# Arduino_S3v3_R2_ft3.net
KiCad netlist of a schematic drawn in EAGLE
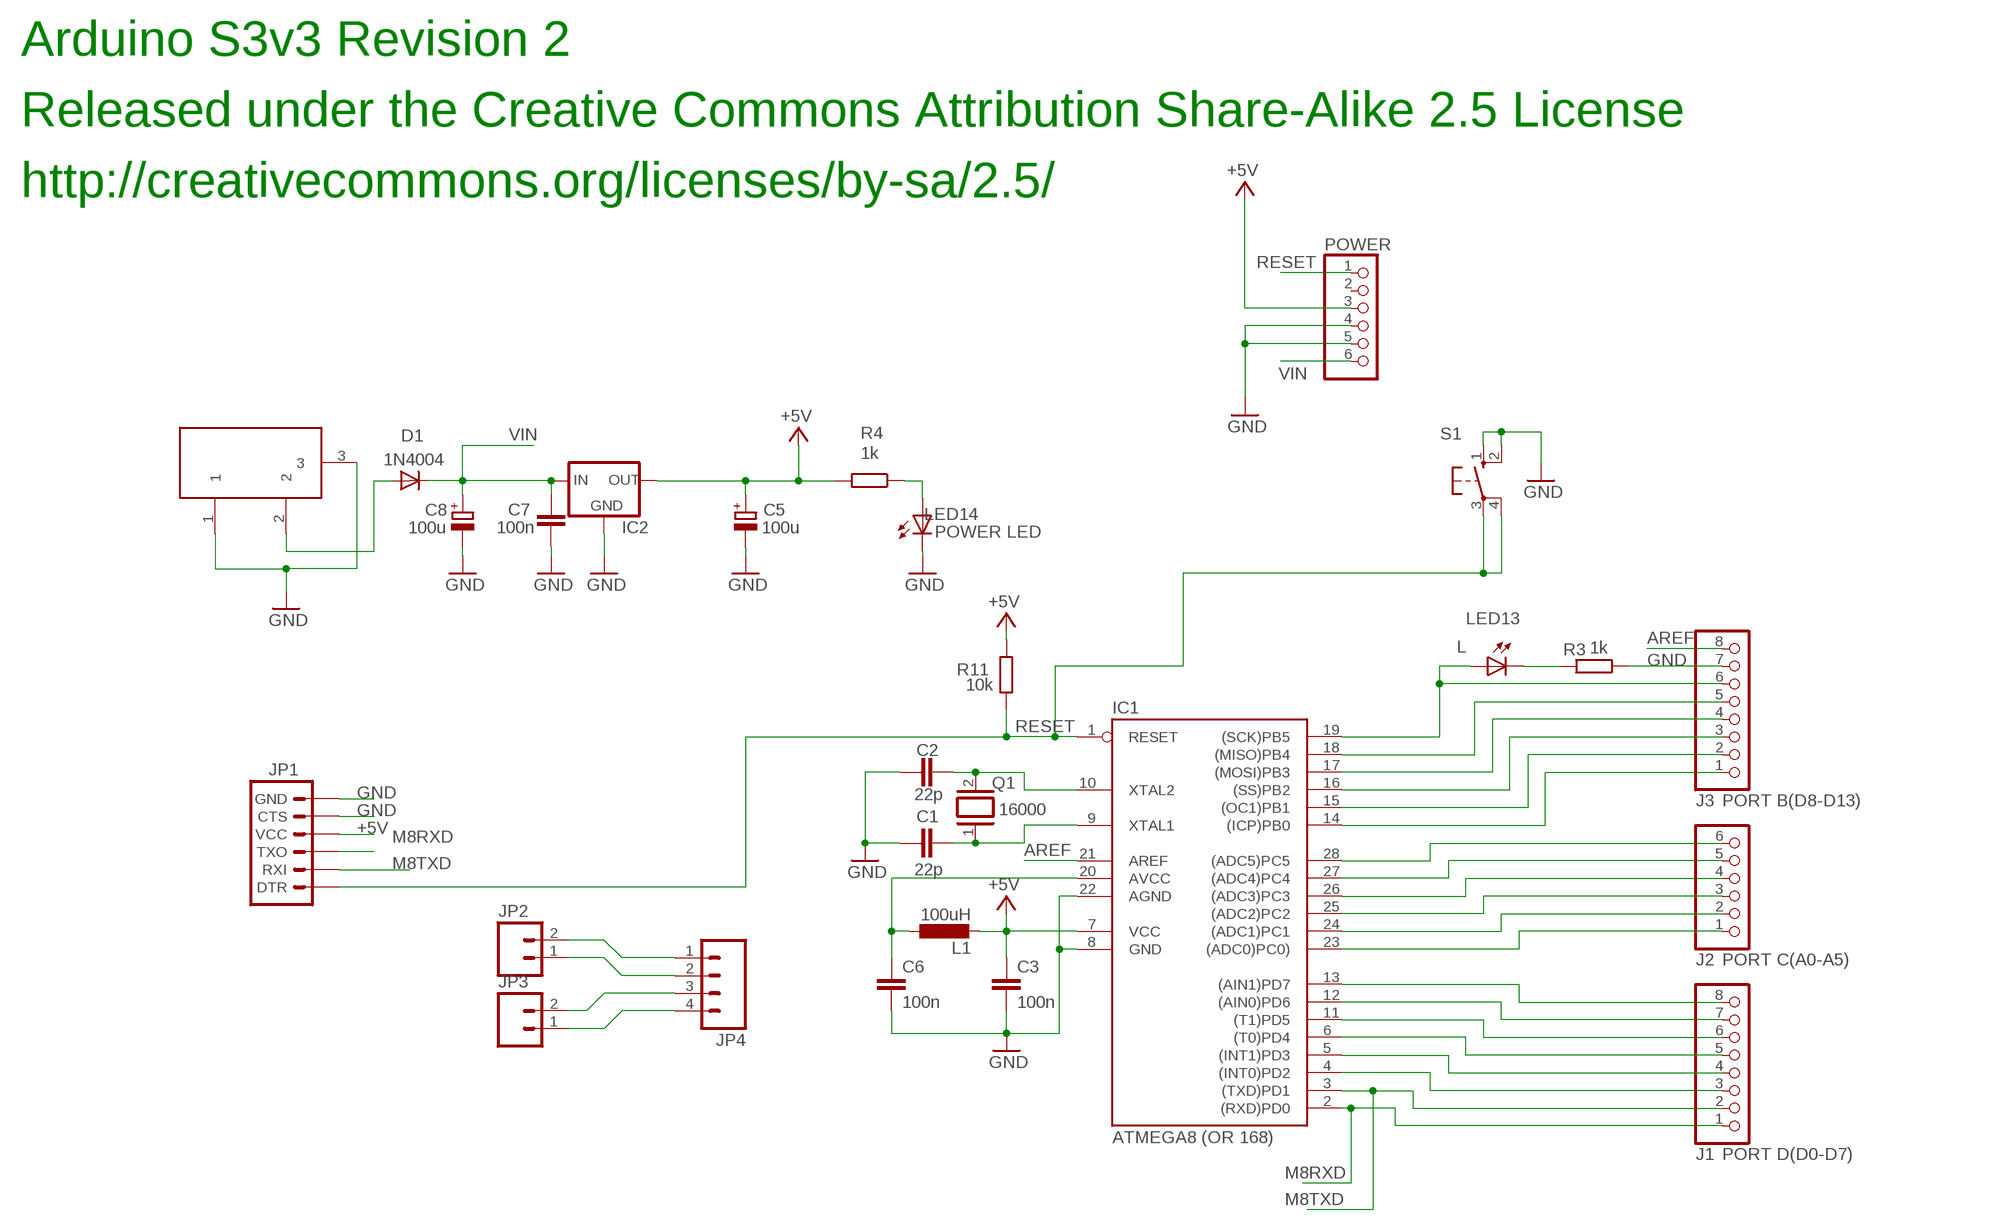
[diagram p0: schematic, sheet 1]

(export (version "E")
  (design (tool "Eeschema 10.0.6"))
  (components
    (comp (ref "C1")
      (value "22p")
      (footprint "eagle-import:C050-025X075")
      (libsource (lib "eagle-import") (part "C-EU050-025X075"))
    )
    (comp (ref "C2")
      (value "22p")
      (footprint "eagle-import:C050-025X075")
      (libsource (lib "eagle-import") (part "C-EU050-025X075"))
    )
    (comp (ref "C3")
      (value "100n")
      (footprint "eagle-import:C050-025X075")
      (libsource (lib "eagle-import") (part "C-EU050-025X075"))
    )
    (comp (ref "C5")
      (value "100u")
      (footprint "eagle-import:E3,5-8")
      (libsource (lib "eagle-import") (part "CPOL-EUE3.5-8"))
    )
    (comp (ref "C6")
      (value "100n")
      (footprint "eagle-import:C050-025X075")
      (libsource (lib "eagle-import") (part "C-EU050-025X075"))
    )
    (comp (ref "C7")
      (value "100n")
      (footprint "eagle-import:C050-025X075")
      (libsource (lib "eagle-import") (part "C-EU050-025X075"))
    )
    (comp (ref "C8")
      (value "100u")
      (footprint "eagle-import:E3,5-8")
      (libsource (lib "eagle-import") (part "CPOL-EUE3.5-8"))
    )
    (comp (ref "D1")
      (value "1N4004")
      (footprint "eagle-import:DO41-10")
      (libsource (lib "eagle-import") (part "1N4004"))
    )
    (comp (ref "DC1")
      (value "DC21MMX")
      (footprint "eagle-import:DC-21MM")
      (libsource (lib "eagle-import") (part "DC21MMX"))
    )
    (comp (ref "IC1")
      (value "ATMEGA8 (OR 168)")
      (footprint "eagle-import:DIL28-3")
      (libsource (lib "eagle-import") (part "AT90S4433P"))
    )
    (comp (ref "IC2")
      (value "78XXL")
      (footprint "eagle-import:78XXL")
      (libsource (lib "eagle-import") (part "78XXL"))
    )
    (comp (ref "J1")
      (value "PORT D(D0-D7)")
      (footprint "eagle-import:1X08")
      (libsource (lib "eagle-import") (part "PINHD-1X8"))
    )
    (comp (ref "J2")
      (value "PORT C(A0-A5)")
      (footprint "eagle-import:1X06")
      (libsource (lib "eagle-import") (part "PINHD-1X6"))
    )
    (comp (ref "J3")
      (value "PORT B(D8-D13)")
      (footprint "eagle-import:1X08")
      (libsource (lib "eagle-import") (part "PINHD-1X8"))
    )
    (comp (ref "JP1")
      (value "ARDUINO_SERIAL_PROGRAMLONGPADS")
      (footprint "eagle-import:1X06_LONGPADS")
      (libsource (lib "eagle-import") (part "ARDUINO_SERIAL_PROGRAMLONGPADS"))
    )
    (comp (ref "JP2")
      (value "M025MM")
      (footprint "eagle-import:SCREWTERMINAL-5MM-2")
      (libsource (lib "eagle-import") (part "M025MM"))
    )
    (comp (ref "JP3")
      (value "M025MM")
      (footprint "eagle-import:SCREWTERMINAL-5MM-2")
      (libsource (lib "eagle-import") (part "M025MM"))
    )
    (comp (ref "JP4")
      (value "M04LONGPADS")
      (footprint "eagle-import:1X04_LONGPADS")
      (libsource (lib "eagle-import") (part "M04LONGPADS"))
    )
    (comp (ref "L1")
      (value "100uH")
      (footprint "eagle-import:0207_10")
      (libsource (lib "eagle-import") (part "L-EU0207/10"))
    )
    (comp (ref "LED13")
      (value "L")
      (footprint "eagle-import:LED3MM")
      (libsource (lib "eagle-import") (part "LED3MM"))
    )
    (comp (ref "LED14")
      (value "POWER LED")
      (footprint "eagle-import:LED3MM")
      (libsource (lib "eagle-import") (part "LED3MM"))
    )
    (comp (ref "POWER")
      (value "PINHD-1X6")
      (footprint "eagle-import:1X06")
      (libsource (lib "eagle-import") (part "PINHD-1X6"))
    )
    (comp (ref "Q1")
      (value "16000")
      (footprint "eagle-import:Q")
      (libsource (lib "eagle-import") (part "XTAL"))
    )
    (comp (ref "R3")
      (value "1k")
      (footprint "eagle-import:0207_10")
      (libsource (lib "eagle-import") (part "R-EU_0207/10"))
    )
    (comp (ref "R4")
      (value "1k")
      (footprint "eagle-import:0207_10")
      (libsource (lib "eagle-import") (part "R-EU_0207/10"))
    )
    (comp (ref "R11")
      (value "10k")
      (footprint "eagle-import:0207_10")
      (libsource (lib "eagle-import") (part "R-EU_0207/10"))
    )
    (comp (ref "S1")
      (value "10-XX")
      (footprint "eagle-import:B3F-10XX")
      (libsource (lib "eagle-import") (part "10-XX"))
    )
  )
  (nets
    (net (code "1") (name "+5V") (class "Default")
      (node (ref "C3") (pin "1") (pinfunction "1_1") (pintype "passive"))
      (node (ref "C5") (pin "+") (pinfunction "+_+") (pintype "passive"))
      (node (ref "IC1") (pin "7") (pinfunction "VCC_7") (pintype "power_in"))
      (node (ref "IC2") (pin "OUT") (pinfunction "OUT_OUT") (pintype "passive"))
      (node (ref "JP1") (pin "4") (pinfunction "VCC_4") (pintype "passive"))
      (node (ref "L1") (pin "2") (pinfunction "2_2") (pintype "passive"))
      (node (ref "POWER") (pin "3") (pinfunction "3_3") (pintype "passive"))
      (node (ref "R11") (pin "2") (pinfunction "2_2") (pintype "passive"))
      (node (ref "R4") (pin "2") (pinfunction "2_2") (pintype "passive"))
    )
    (net (code "2") (name "/AREF") (class "Default")
      (node (ref "IC1") (pin "21") (pinfunction "AREF_21") (pintype "power_in"))
      (node (ref "J3") (pin "8") (pinfunction "8_8") (pintype "passive"))
    )
    (net (code "3") (name "/M8RXD") (class "Default")
      (node (ref "IC1") (pin "2") (pinfunction "(RXD)PD0_2") (pintype "bidirectional"))
      (node (ref "J1") (pin "1") (pinfunction "1_1") (pintype "passive"))
      (node (ref "JP1") (pin "3") (pinfunction "TXO_3") (pintype "passive"))
    )
    (net (code "4") (name "/M8TXD") (class "Default")
      (node (ref "IC1") (pin "3") (pinfunction "(TXD)PD1_3") (pintype "bidirectional"))
      (node (ref "J1") (pin "2") (pinfunction "2_2") (pintype "passive"))
      (node (ref "JP1") (pin "2") (pinfunction "RXI_2") (pintype "passive"))
    )
    (net (code "5") (name "/RESET") (class "Default")
      (node (ref "IC1") (pin "1") (pinfunction "RESET_1") (pintype "input"))
      (node (ref "JP1") (pin "1") (pinfunction "DTR_1") (pintype "passive"))
      (node (ref "POWER") (pin "1") (pinfunction "1_1") (pintype "passive"))
      (node (ref "R11") (pin "1") (pinfunction "1_1") (pintype "passive"))
      (node (ref "S1") (pin "3") (pinfunction "P_3") (pintype "passive"))
      (node (ref "S1") (pin "4") (pinfunction "P1_4") (pintype "passive"))
    )
    (net (code "6") (name "/VIN") (class "Default")
      (node (ref "C7") (pin "2") (pinfunction "2_2") (pintype "passive"))
      (node (ref "C8") (pin "+") (pinfunction "+_+") (pintype "passive"))
      (node (ref "D1") (pin "C") (pinfunction "C_C") (pintype "passive"))
      (node (ref "IC2") (pin "IN") (pinfunction "IN_IN") (pintype "input"))
      (node (ref "POWER") (pin "6") (pinfunction "6_6") (pintype "passive"))
    )
    (net (code "7") (name "GND") (class "Default")
      (node (ref "C1") (pin "1") (pinfunction "1_1") (pintype "passive"))
      (node (ref "C2") (pin "1") (pinfunction "1_1") (pintype "passive"))
      (node (ref "C3") (pin "2") (pinfunction "2_2") (pintype "passive"))
      (node (ref "C5") (pin "-") (pinfunction "-_-") (pintype "passive"))
      (node (ref "C6") (pin "2") (pinfunction "2_2") (pintype "passive"))
      (node (ref "C7") (pin "1") (pinfunction "1_1") (pintype "passive"))
      (node (ref "C8") (pin "-") (pinfunction "-_-") (pintype "passive"))
      (node (ref "DC1") (pin "1") (pinfunction "1_1") (pintype "power_in"))
      (node (ref "DC1") (pin "3") (pinfunction "3_3") (pintype "power_in"))
      (node (ref "IC1") (pin "22") (pinfunction "AGND_22") (pintype "power_in"))
      (node (ref "IC1") (pin "8") (pinfunction "GND_8") (pintype "power_in"))
      (node (ref "IC2") (pin "GND") (pinfunction "GND_GND") (pintype "input"))
      (node (ref "J3") (pin "7") (pinfunction "7_7") (pintype "passive"))
      (node (ref "JP1") (pin "5") (pinfunction "CTS_5") (pintype "passive"))
      (node (ref "JP1") (pin "6") (pinfunction "GND_6") (pintype "passive"))
      (node (ref "LED14") (pin "K") (pinfunction "C_K") (pintype "passive"))
      (node (ref "POWER") (pin "4") (pinfunction "4_4") (pintype "passive"))
      (node (ref "POWER") (pin "5") (pinfunction "5_5") (pintype "passive"))
      (node (ref "R3") (pin "1") (pinfunction "1_1") (pintype "passive"))
      (node (ref "S1") (pin "1") (pinfunction "S_1") (pintype "passive"))
      (node (ref "S1") (pin "2") (pinfunction "S1_2") (pintype "passive"))
    )
    (net (code "8") (name "Net-(D1-PadA)") (class "Default")
      (node (ref "D1") (pin "A") (pinfunction "A_A") (pintype "passive"))
      (node (ref "DC1") (pin "2") (pinfunction "2_2") (pintype "power_in"))
    )
    (net (code "9") (name "Net-(IC1-(ADC0)PC0))") (class "Default")
      (node (ref "IC1") (pin "23") (pinfunction "(ADC0)PC0)_23") (pintype "bidirectional"))
      (node (ref "J2") (pin "1") (pinfunction "1_1") (pintype "passive"))
    )
    (net (code "10") (name "Net-(IC1-(ADC1)PC1)") (class "Default")
      (node (ref "IC1") (pin "24") (pinfunction "(ADC1)PC1_24") (pintype "bidirectional"))
      (node (ref "J2") (pin "2") (pinfunction "2_2") (pintype "passive"))
    )
    (net (code "11") (name "Net-(IC1-(ADC2)PC2)") (class "Default")
      (node (ref "IC1") (pin "25") (pinfunction "(ADC2)PC2_25") (pintype "bidirectional"))
      (node (ref "J2") (pin "3") (pinfunction "3_3") (pintype "passive"))
    )
    (net (code "12") (name "Net-(IC1-(ADC3)PC3)") (class "Default")
      (node (ref "IC1") (pin "26") (pinfunction "(ADC3)PC3_26") (pintype "bidirectional"))
      (node (ref "J2") (pin "4") (pinfunction "4_4") (pintype "passive"))
    )
    (net (code "13") (name "Net-(IC1-(ADC4)PC4)") (class "Default")
      (node (ref "IC1") (pin "27") (pinfunction "(ADC4)PC4_27") (pintype "bidirectional"))
      (node (ref "J2") (pin "5") (pinfunction "5_5") (pintype "passive"))
    )
    (net (code "14") (name "Net-(IC1-(ADC5)PC5)") (class "Default")
      (node (ref "IC1") (pin "28") (pinfunction "(ADC5)PC5_28") (pintype "bidirectional"))
      (node (ref "J2") (pin "6") (pinfunction "6_6") (pintype "passive"))
    )
    (net (code "15") (name "Net-(IC1-(AIN0)PD6)") (class "Default")
      (node (ref "IC1") (pin "12") (pinfunction "(AIN0)PD6_12") (pintype "bidirectional"))
      (node (ref "J1") (pin "7") (pinfunction "7_7") (pintype "passive"))
    )
    (net (code "16") (name "Net-(IC1-(AIN1)PD7)") (class "Default")
      (node (ref "IC1") (pin "13") (pinfunction "(AIN1)PD7_13") (pintype "bidirectional"))
      (node (ref "J1") (pin "8") (pinfunction "8_8") (pintype "passive"))
    )
    (net (code "17") (name "Net-(IC1-(ICP)PB0)") (class "Default")
      (node (ref "IC1") (pin "14") (pinfunction "(ICP)PB0_14") (pintype "bidirectional"))
      (node (ref "J3") (pin "1") (pinfunction "1_1") (pintype "passive"))
    )
    (net (code "18") (name "Net-(IC1-(INT0)PD2)") (class "Default")
      (node (ref "IC1") (pin "4") (pinfunction "(INT0)PD2_4") (pintype "bidirectional"))
      (node (ref "J1") (pin "3") (pinfunction "3_3") (pintype "passive"))
    )
    (net (code "19") (name "Net-(IC1-(INT1)PD3)") (class "Default")
      (node (ref "IC1") (pin "5") (pinfunction "(INT1)PD3_5") (pintype "bidirectional"))
      (node (ref "J1") (pin "4") (pinfunction "4_4") (pintype "passive"))
    )
    (net (code "20") (name "Net-(IC1-(MISO)PB4)") (class "Default")
      (node (ref "IC1") (pin "18") (pinfunction "(MISO)PB4_18") (pintype "bidirectional"))
      (node (ref "J3") (pin "5") (pinfunction "5_5") (pintype "passive"))
    )
    (net (code "21") (name "Net-(IC1-(MOSI)PB3)") (class "Default")
      (node (ref "IC1") (pin "17") (pinfunction "(MOSI)PB3_17") (pintype "bidirectional"))
      (node (ref "J3") (pin "4") (pinfunction "4_4") (pintype "passive"))
    )
    (net (code "22") (name "Net-(IC1-(OC1)PB1)") (class "Default")
      (node (ref "IC1") (pin "15") (pinfunction "(OC1)PB1_15") (pintype "bidirectional"))
      (node (ref "J3") (pin "2") (pinfunction "2_2") (pintype "passive"))
    )
    (net (code "23") (name "Net-(IC1-(SCK)PB5)") (class "Default")
      (node (ref "IC1") (pin "19") (pinfunction "(SCK)PB5_19") (pintype "bidirectional"))
      (node (ref "J3") (pin "6") (pinfunction "6_6") (pintype "passive"))
      (node (ref "LED13") (pin "A") (pinfunction "A_A") (pintype "passive"))
    )
    (net (code "24") (name "Net-(IC1-(SS)PB2)") (class "Default")
      (node (ref "IC1") (pin "16") (pinfunction "(SS)PB2_16") (pintype "bidirectional"))
      (node (ref "J3") (pin "3") (pinfunction "3_3") (pintype "passive"))
    )
    (net (code "25") (name "Net-(IC1-(T0)PD4)") (class "Default")
      (node (ref "IC1") (pin "6") (pinfunction "(T0)PD4_6") (pintype "bidirectional"))
      (node (ref "J1") (pin "5") (pinfunction "5_5") (pintype "passive"))
    )
    (net (code "26") (name "Net-(IC1-(T1)PD5)") (class "Default")
      (node (ref "IC1") (pin "11") (pinfunction "(T1)PD5_11") (pintype "bidirectional"))
      (node (ref "J1") (pin "6") (pinfunction "6_6") (pintype "passive"))
    )
    (net (code "27") (name "Net-(IC1-AVCC)") (class "Default")
      (node (ref "C6") (pin "1") (pinfunction "1_1") (pintype "passive"))
      (node (ref "IC1") (pin "20") (pinfunction "AVCC_20") (pintype "power_in"))
      (node (ref "L1") (pin "1") (pinfunction "1_1") (pintype "passive"))
    )
    (net (code "28") (name "Net-(IC1-XTAL1)") (class "Default")
      (node (ref "C1") (pin "2") (pinfunction "2_2") (pintype "passive"))
      (node (ref "IC1") (pin "9") (pinfunction "XTAL1_9") (pintype "bidirectional"))
      (node (ref "Q1") (pin "1") (pinfunction "1_1") (pintype "passive"))
    )
    (net (code "29") (name "Net-(IC1-XTAL2)") (class "Default")
      (node (ref "C2") (pin "2") (pinfunction "2_2") (pintype "passive"))
      (node (ref "IC1") (pin "10") (pinfunction "XTAL2_10") (pintype "bidirectional"))
      (node (ref "Q1") (pin "2") (pinfunction "2_2") (pintype "passive"))
    )
    (net (code "30") (name "Net-(JP2-Pad1)") (class "Default")
      (node (ref "JP2") (pin "1") (pinfunction "1_1") (pintype "passive"))
      (node (ref "JP4") (pin "2") (pinfunction "2_2") (pintype "passive"))
    )
    (net (code "31") (name "Net-(JP2-Pad2)") (class "Default")
      (node (ref "JP2") (pin "2") (pinfunction "2_2") (pintype "passive"))
      (node (ref "JP4") (pin "1") (pinfunction "1_1") (pintype "passive"))
    )
    (net (code "32") (name "Net-(JP3-Pad1)") (class "Default")
      (node (ref "JP3") (pin "1") (pinfunction "1_1") (pintype "passive"))
      (node (ref "JP4") (pin "4") (pinfunction "4_4") (pintype "passive"))
    )
    (net (code "33") (name "Net-(JP3-Pad2)") (class "Default")
      (node (ref "JP3") (pin "2") (pinfunction "2_2") (pintype "passive"))
      (node (ref "JP4") (pin "3") (pinfunction "3_3") (pintype "passive"))
    )
    (net (code "34") (name "Net-(LED13-C)") (class "Default")
      (node (ref "LED13") (pin "K") (pinfunction "C_K") (pintype "passive"))
      (node (ref "R3") (pin "2") (pinfunction "2_2") (pintype "passive"))
    )
    (net (code "35") (name "Net-(LED14-PadA)") (class "Default")
      (node (ref "LED14") (pin "A") (pinfunction "A_A") (pintype "passive"))
      (node (ref "R4") (pin "1") (pinfunction "1_1") (pintype "passive"))
    )
    (net (code "36") (name "unconnected-(POWER-Pad2)") (class "Default")
      (node (ref "POWER") (pin "2") (pinfunction "2_2") (pintype "passive"))
    )
  )
)
